# SparkFun_Ultrasonic_Sensor.net
KiCad netlist of a schematic drawn in EAGLE
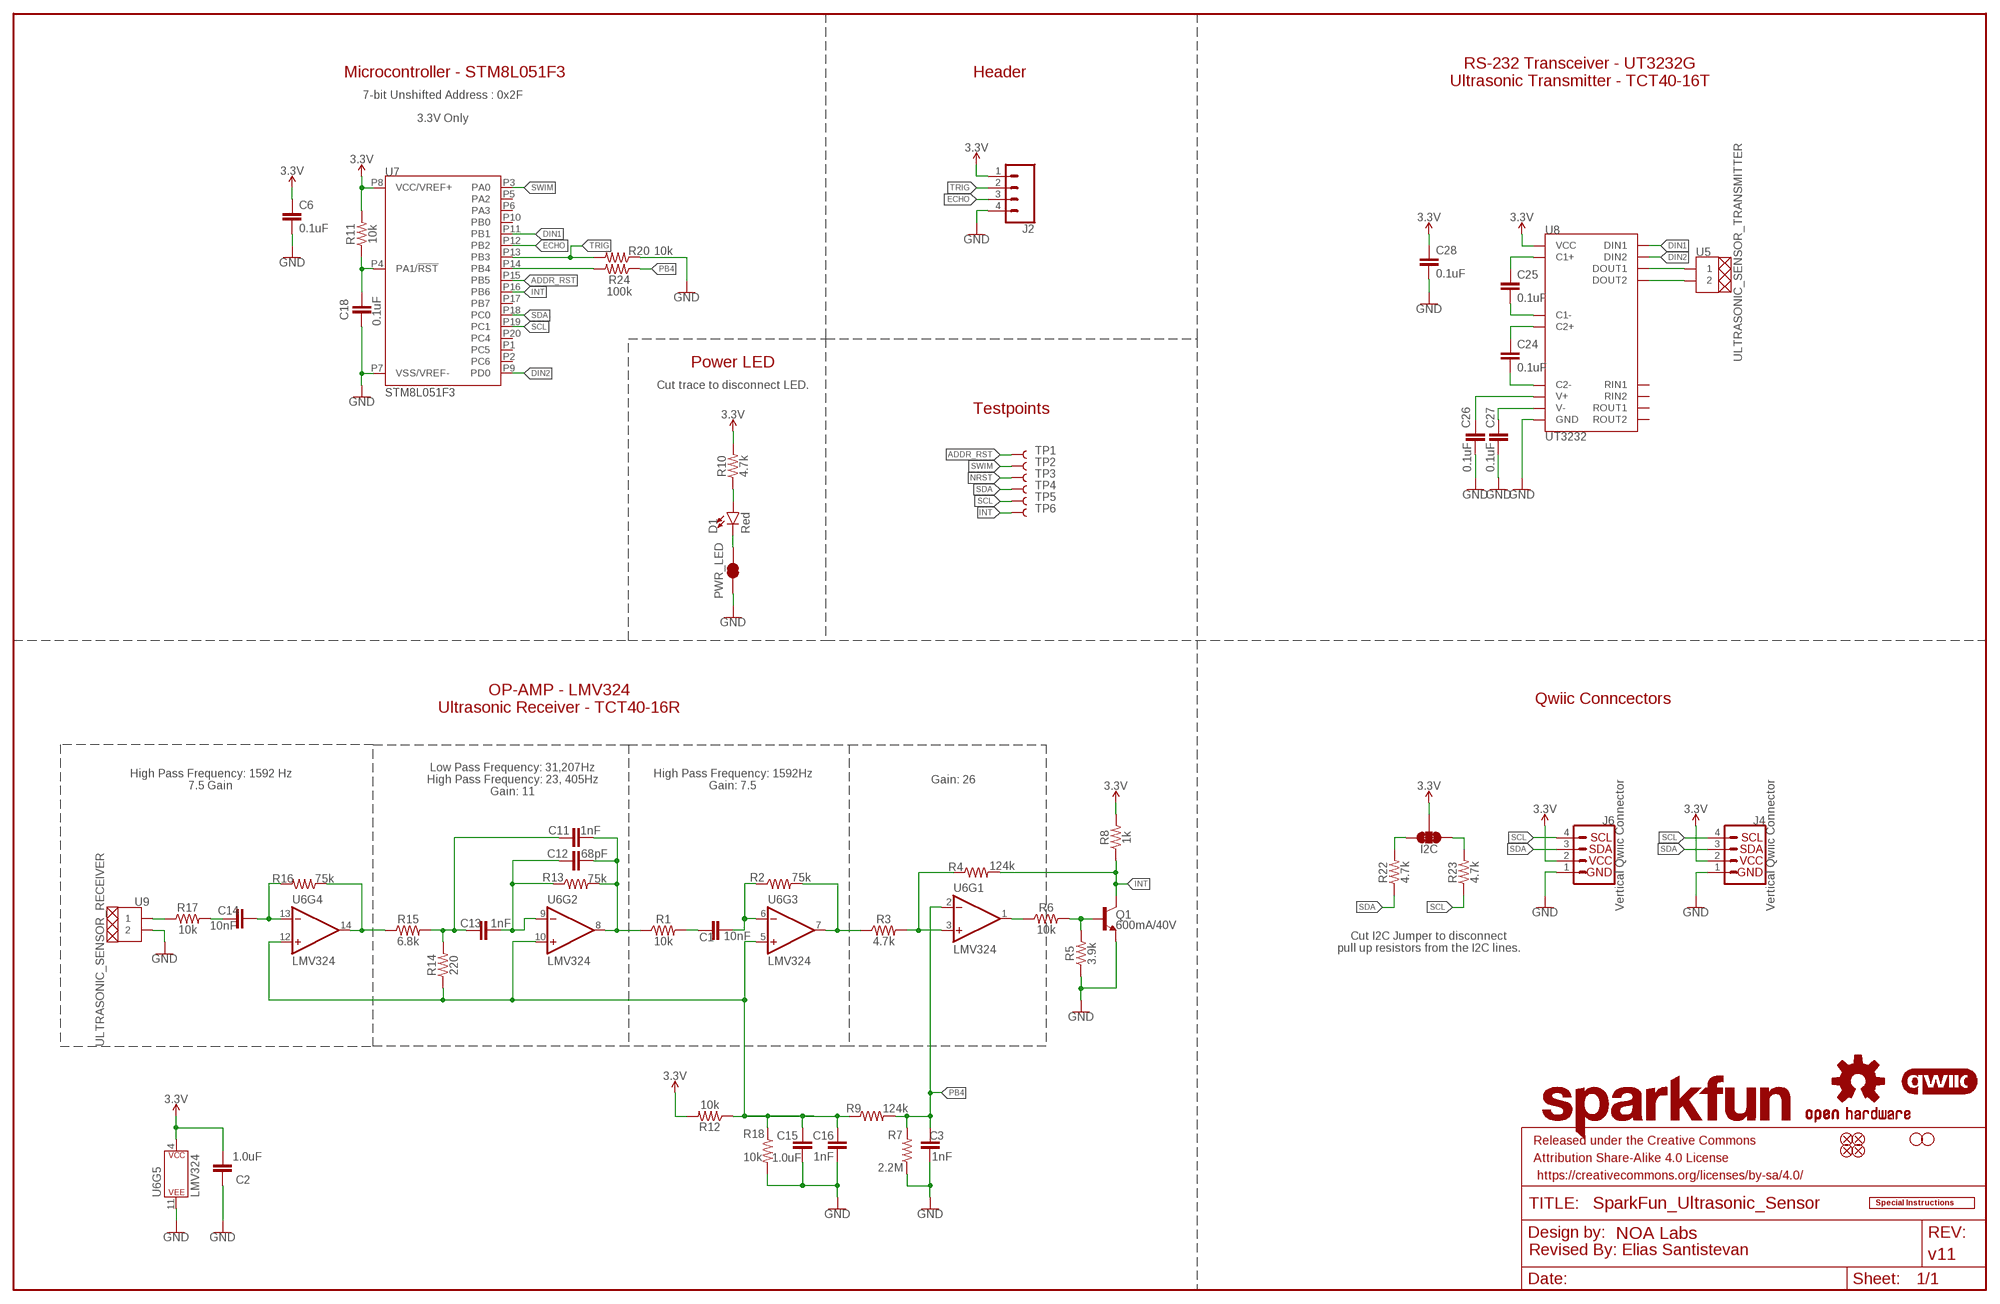
[diagram p0: schematic, sheet 1]

(export (version "E")
  (design (tool "Eeschema 10.0.6"))
  (components
    (comp (ref "C1")
      (value "10nF")
      (footprint "eagle-import:0603")
      (libsource (lib "eagle-import") (part "10NF-0603-50V-10%"))
    )
    (comp (ref "C2")
      (value "1.0uF")
      (footprint "eagle-import:0603")
      (libsource (lib "eagle-import") (part "1.0UF-0603-16V-10%"))
    )
    (comp (ref "C3")
      (value "1nF")
      (footprint "eagle-import:0603")
      (libsource (lib "eagle-import") (part "1.0NF/1000PF-0603-50V-10%"))
    )
    (comp (ref "C6")
      (value "0.1uF")
      (footprint "eagle-import:0603")
      (libsource (lib "eagle-import") (part "0.1UF-0603-25V-(+80/-20%)"))
    )
    (comp (ref "C11")
      (value "1nF")
      (footprint "eagle-import:0603")
      (libsource (lib "eagle-import") (part "1.0NF/1000PF-0603-50V-10%"))
    )
    (comp (ref "C12")
      (value "68pF")
      (footprint "eagle-import:0603")
      (libsource (lib "eagle-import") (part "68PF-0603-50V-5%"))
    )
    (comp (ref "C13")
      (value "1nF")
      (footprint "eagle-import:0603")
      (libsource (lib "eagle-import") (part "1.0NF/1000PF-0603-50V-10%"))
    )
    (comp (ref "C14")
      (value "10nF")
      (footprint "eagle-import:0603")
      (libsource (lib "eagle-import") (part "10NF-0603-50V-10%"))
    )
    (comp (ref "C15")
      (value "1.0uF")
      (footprint "eagle-import:0603")
      (libsource (lib "eagle-import") (part "1.0UF-0603-16V-10%"))
    )
    (comp (ref "C16")
      (value "1nF")
      (footprint "eagle-import:0603")
      (libsource (lib "eagle-import") (part "1.0NF/1000PF-0603-50V-10%"))
    )
    (comp (ref "C18")
      (value "0.1uF")
      (footprint "eagle-import:0603")
      (libsource (lib "eagle-import") (part "0.1UF-0603-25V-(+80/-20%)"))
    )
    (comp (ref "C24")
      (value "0.1uF")
      (footprint "eagle-import:0603")
      (libsource (lib "eagle-import") (part "0.1UF-0603-25V-(+80/-20%)"))
    )
    (comp (ref "C25")
      (value "0.1uF")
      (footprint "eagle-import:0603")
      (libsource (lib "eagle-import") (part "0.1UF-0603-25V-(+80/-20%)"))
    )
    (comp (ref "C26")
      (value "0.1uF")
      (footprint "eagle-import:0603")
      (libsource (lib "eagle-import") (part "0.1UF-0603-25V-(+80/-20%)"))
    )
    (comp (ref "C27")
      (value "0.1uF")
      (footprint "eagle-import:0603")
      (libsource (lib "eagle-import") (part "0.1UF-0603-25V-(+80/-20%)"))
    )
    (comp (ref "C28")
      (value "0.1uF")
      (footprint "eagle-import:0603")
      (libsource (lib "eagle-import") (part "0.1UF-0603-25V-(+80/-20%)"))
    )
    (comp (ref "D1")
      (value "Red")
      (footprint "eagle-import:LED-0603")
      (libsource (lib "eagle-import") (part "LED-RED_0603-KB"))
    )
    (comp (ref "FD1")
      (value "FIDUCIAL1X2")
      (footprint "eagle-import:FIDUCIAL-1X2")
      (libsource (lib "eagle-import") (part "FIDUCIAL1X2"))
    )
    (comp (ref "FD2")
      (value "FIDUCIAL1X2")
      (footprint "eagle-import:FIDUCIAL-1X2")
      (libsource (lib "eagle-import") (part "FIDUCIAL1X2"))
    )
    (comp (ref "FD3")
      (value "FIDUCIAL1X2")
      (footprint "eagle-import:FIDUCIAL-1X2")
      (libsource (lib "eagle-import") (part "FIDUCIAL1X2"))
    )
    (comp (ref "FD4")
      (value "FIDUCIAL1X2")
      (footprint "eagle-import:FIDUCIAL-1X2")
      (libsource (lib "eagle-import") (part "FIDUCIAL1X2"))
    )
    (comp (ref "FRAME1")
      (value "FRAME-LEDGER")
      (footprint "eagle-import:CREATIVE_COMMONS")
      (fields (field (name "DESIGNER") "NOA Labs") (field (name "REV") "v11"))
      (libsource (lib "eagle-import") (part "FRAME-LEDGER"))
    )
    (comp (ref "H1")
      (value "STAND-OFFTIGHT")
      (footprint "eagle-import:STAND-OFF-TIGHT")
      (libsource (lib "eagle-import") (part "STAND-OFFTIGHT"))
    )
    (comp (ref "H2")
      (value "STAND-OFFTIGHT")
      (footprint "eagle-import:STAND-OFF-TIGHT")
      (libsource (lib "eagle-import") (part "STAND-OFFTIGHT"))
    )
    (comp (ref "I2C")
      (value "JUMPER-SMT_3_2-NC_TRACE_SILK")
      (footprint "eagle-import:SMT-JUMPER_3_2-NC_TRACE_SILK")
      (libsource (lib "eagle-import") (part "JUMPER-SMT_3_2-NC_TRACE_SILK"))
    )
    (comp (ref "J2")
      (value "CONN_041X04_NO_SILK_NO_POP")
      (footprint "eagle-import:1X04_NO_SILK")
      (libsource (lib "eagle-import") (part "CONN_041X04_NO_SILK_NO_POP"))
    )
    (comp (ref "J4")
      (value "Vertical Qwiic Connector")
      (footprint "eagle-import:JST04_1MM_VERT")
      (libsource (lib "eagle-import") (part "QWIIC_CONNECTOR"))
    )
    (comp (ref "J6")
      (value "Vertical Qwiic Connector")
      (footprint "eagle-import:JST04_1MM_VERT")
      (libsource (lib "eagle-import") (part "QWIIC_CONNECTOR"))
    )
    (comp (ref "LOGO1")
      (value "SPECIAL_INSTRUCTIONS-ORDERING")
      (footprint "eagle-import:ORDERING_INSTRUCTIONS")
      (libsource (lib "eagle-import") (part "SPECIAL_INSTRUCTIONS-ORDERING"))
    )
    (comp (ref "LOGO2")
      (value "SFE_LOGO_NAME.1_INCH")
      (footprint "eagle-import:SFE_LOGO_NAME_.1")
      (libsource (lib "eagle-import") (part "SFE_LOGO_NAME.1_INCH"))
    )
    (comp (ref "LOGO3")
      (value "QWIIC_LOGO_3MM")
      (footprint "eagle-import:QWIIC_3MM")
      (libsource (lib "eagle-import") (part "QWIIC_LOGO_3MM"))
    )
    (comp (ref "LOGO4")
      (value "OSHW-LOGOS")
      (footprint "eagle-import:OSHW-LOGO-S")
      (libsource (lib "eagle-import") (part "OSHW-LOGOS"))
    )
    (comp (ref "PWR_LED")
      (value "JUMPER-SMT_2_NC_TRACE_SILK")
      (footprint "eagle-import:SMT-JUMPER_2_NC_TRACE_SILK")
      (libsource (lib "eagle-import") (part "JUMPER-SMT_2_NC_TRACE_SILK"))
    )
    (comp (ref "Q1")
      (value "600mA/40V")
      (footprint "eagle-import:SOT23-3")
      (libsource (lib "eagle-import") (part "TRANS_NPN-MMBT2222AL"))
    )
    (comp (ref "R1")
      (value "10k")
      (footprint "eagle-import:0603")
      (libsource (lib "eagle-import") (part "10KOHM-0603-1/10W-1%"))
    )
    (comp (ref "R2")
      (value "75k")
      (footprint "eagle-import:0603")
      (libsource (lib "eagle-import") (part "75KOHM-0603-1/10W-1%"))
    )
    (comp (ref "R3")
      (value "4.7k")
      (footprint "eagle-import:0603")
      (libsource (lib "eagle-import") (part "4.7KOHM-0603-1/10W-1%"))
    )
    (comp (ref "R4")
      (value "124k")
      (footprint "eagle-import:0603")
      (libsource (lib "eagle-import") (part "124KOHM"))
    )
    (comp (ref "R5")
      (value "3.9k")
      (footprint "eagle-import:0603")
      (libsource (lib "eagle-import") (part "3.9KOHM-0603-1/10W-1%"))
    )
    (comp (ref "R6")
      (value "10k")
      (footprint "eagle-import:0603")
      (libsource (lib "eagle-import") (part "10KOHM-0603-1/10W-1%"))
    )
    (comp (ref "R7")
      (value "2.2M")
      (footprint "eagle-import:0603")
      (libsource (lib "eagle-import") (part "2.2MOHMS-0603-1/10W-1%"))
    )
    (comp (ref "R8")
      (value "1k")
      (footprint "eagle-import:0603")
      (libsource (lib "eagle-import") (part "1KOHM-0603-1/10W-1%"))
    )
    (comp (ref "R9")
      (value "124k")
      (footprint "eagle-import:0603")
      (libsource (lib "eagle-import") (part "124KOHM"))
    )
    (comp (ref "R10")
      (value "4.7k")
      (footprint "eagle-import:0603")
      (libsource (lib "eagle-import") (part "4.7KOHM-0603-1/10W-1%"))
    )
    (comp (ref "R11")
      (value "10k")
      (footprint "eagle-import:0603")
      (libsource (lib "eagle-import") (part "10KOHM-0603-1/10W-1%"))
    )
    (comp (ref "R12")
      (value "10k")
      (footprint "eagle-import:0603")
      (libsource (lib "eagle-import") (part "10KOHM-0603-1/10W-1%"))
    )
    (comp (ref "R13")
      (value "75k")
      (footprint "eagle-import:0603")
      (libsource (lib "eagle-import") (part "75KOHM-0603-1/10W-1%"))
    )
    (comp (ref "R14")
      (value "220")
      (footprint "eagle-import:0603")
      (libsource (lib "eagle-import") (part "220OHM-0603-1/10W-1%"))
    )
    (comp (ref "R15")
      (value "6.8k")
      (footprint "eagle-import:0603")
      (libsource (lib "eagle-import") (part "6.8KOHM-0603-1/10W-1%"))
    )
    (comp (ref "R16")
      (value "75k")
      (footprint "eagle-import:0603")
      (libsource (lib "eagle-import") (part "75KOHM-0603-1/10W-1%"))
    )
    (comp (ref "R17")
      (value "10k")
      (footprint "eagle-import:0603")
      (libsource (lib "eagle-import") (part "10KOHM-0603-1/10W-1%"))
    )
    (comp (ref "R18")
      (value "10k")
      (footprint "eagle-import:0603")
      (libsource (lib "eagle-import") (part "10KOHM-0603-1/10W-1%"))
    )
    (comp (ref "R20")
      (value "10k")
      (footprint "eagle-import:0603")
      (libsource (lib "eagle-import") (part "10KOHM-0603-1/10W-1%"))
    )
    (comp (ref "R22")
      (value "4.7k")
      (footprint "eagle-import:0603")
      (libsource (lib "eagle-import") (part "4.7KOHM-0603-1/10W-1%"))
    )
    (comp (ref "R23")
      (value "4.7k")
      (footprint "eagle-import:0603")
      (libsource (lib "eagle-import") (part "4.7KOHM-0603-1/10W-1%"))
    )
    (comp (ref "R24")
      (value "100k")
      (footprint "eagle-import:0603")
      (libsource (lib "eagle-import") (part "100KOHM-0603-1/10W-1%"))
    )
    (comp (ref "TP1")
      (value "TEST-POINT3X5")
      (footprint "eagle-import:PAD.03X.05")
      (libsource (lib "eagle-import") (part "TEST-POINT3X5"))
    )
    (comp (ref "TP2")
      (value "TEST-POINT3X5")
      (footprint "eagle-import:PAD.03X.05")
      (libsource (lib "eagle-import") (part "TEST-POINT3X5"))
    )
    (comp (ref "TP3")
      (value "TEST-POINT3X5")
      (footprint "eagle-import:PAD.03X.05")
      (libsource (lib "eagle-import") (part "TEST-POINT3X5"))
    )
    (comp (ref "TP4")
      (value "TEST-POINT3X5")
      (footprint "eagle-import:PAD.03X.05")
      (libsource (lib "eagle-import") (part "TEST-POINT3X5"))
    )
    (comp (ref "TP5")
      (value "TEST-POINT3X5")
      (footprint "eagle-import:PAD.03X.05")
      (libsource (lib "eagle-import") (part "TEST-POINT3X5"))
    )
    (comp (ref "TP6")
      (value "TEST-POINT3X5")
      (footprint "eagle-import:PAD.03X.05")
      (libsource (lib "eagle-import") (part "TEST-POINT3X5"))
    )
    (comp (ref "U5")
      (value "ULTRASONIC_SENSOR_TRANSMITTER")
      (footprint "eagle-import:TFT40-16T")
      (libsource (lib "eagle-import") (part "ULTRASONIC_SENSOR_TRANSMITTER"))
    )
    (comp (ref "U6")
      (value "LMV324")
      (footprint "eagle-import:SO14")
      (libsource (lib "eagle-import") (part "LMV324"))
    )
    (comp (ref "U7")
      (value "STM8L051F3")
      (footprint "eagle-import:TSSOP20")
      (libsource (lib "eagle-import") (part "STM8L051F3"))
    )
    (comp (ref "U8")
      (value "UT3232")
      (footprint "eagle-import:TSSOP16")
      (libsource (lib "eagle-import") (part "UT3232"))
    )
    (comp (ref "U9")
      (value "ULTRASONIC_SENSOR_RECEIVER")
      (footprint "eagle-import:TCT40-16R")
      (libsource (lib "eagle-import") (part "ULTRASONIC_SENSOR_RECEIVER"))
    )
  )
  (nets
    (net (code "1") (name "3.3V") (class "Default")
      (node (ref "C2") (pin "2") (pinfunction "2_2") (pintype "passive"))
      (node (ref "C28") (pin "1") (pinfunction "1_1") (pintype "passive"))
      (node (ref "C6") (pin "1") (pinfunction "1_1") (pintype "passive"))
      (node (ref "I2C") (pin "2") (pinfunction "2_2") (pintype "passive"))
      (node (ref "J2") (pin "1") (pinfunction "1_1") (pintype "passive"))
      (node (ref "J4") (pin "2") (pinfunction "2_2") (pintype "power_in"))
      (node (ref "J6") (pin "2") (pinfunction "2_2") (pintype "power_in"))
      (node (ref "R10") (pin "2") (pinfunction "2_2") (pintype "passive"))
      (node (ref "R11") (pin "2") (pinfunction "2_2") (pintype "passive"))
      (node (ref "R12") (pin "2") (pinfunction "2_2") (pintype "passive"))
      (node (ref "R8") (pin "2") (pinfunction "2_2") (pintype "passive"))
      (node (ref "U6") (pin "4") (pinfunction "P$V+_4") (pintype "bidirectional"))
      (node (ref "U7") (pin "P8") (pinfunction "VCC/VREF+_P8") (pintype "bidirectional"))
      (node (ref "U8") (pin "P16") (pinfunction "VCC_P16") (pintype "bidirectional"))
    )
    (net (code "2") (name "ADDR_RST") (class "Default")
      (node (ref "TP1") (pin "1") (pinfunction "1_1") (pintype "bidirectional"))
      (node (ref "U7") (pin "P15") (pinfunction "PB5_P15") (pintype "bidirectional"))
    )
    (net (code "3") (name "DIN1") (class "Default")
      (node (ref "U7") (pin "P11") (pinfunction "PB1_P11") (pintype "bidirectional"))
      (node (ref "U8") (pin "P11") (pinfunction "DIN1_P11") (pintype "bidirectional"))
    )
    (net (code "4") (name "DIN2") (class "Default")
      (node (ref "U7") (pin "P9") (pinfunction "PD0_P9") (pintype "bidirectional"))
      (node (ref "U8") (pin "P10") (pinfunction "DIN2_P10") (pintype "bidirectional"))
    )
    (net (code "5") (name "ECHO") (class "Default")
      (node (ref "J2") (pin "3") (pinfunction "3_3") (pintype "passive"))
      (node (ref "U7") (pin "P12") (pinfunction "PB2_P12") (pintype "bidirectional"))
    )
    (net (code "6") (name "GND") (class "Default")
      (node (ref "C15") (pin "1") (pinfunction "1_1") (pintype "passive"))
      (node (ref "C16") (pin "1") (pinfunction "1_1") (pintype "passive"))
      (node (ref "C18") (pin "2") (pinfunction "2_2") (pintype "passive"))
      (node (ref "C2") (pin "1") (pinfunction "1_1") (pintype "passive"))
      (node (ref "C26") (pin "2") (pinfunction "2_2") (pintype "passive"))
      (node (ref "C27") (pin "2") (pinfunction "2_2") (pintype "passive"))
      (node (ref "C28") (pin "2") (pinfunction "2_2") (pintype "passive"))
      (node (ref "C3") (pin "2") (pinfunction "2_2") (pintype "passive"))
      (node (ref "C6") (pin "2") (pinfunction "2_2") (pintype "passive"))
      (node (ref "J2") (pin "4") (pinfunction "4_4") (pintype "passive"))
      (node (ref "J4") (pin "1") (pinfunction "1_1") (pintype "power_in"))
      (node (ref "J6") (pin "1") (pinfunction "1_1") (pintype "power_in"))
      (node (ref "PWR_LED") (pin "1") (pinfunction "1_1") (pintype "passive"))
      (node (ref "Q1") (pin "2") (pinfunction "E_2") (pintype "passive"))
      (node (ref "R18") (pin "2") (pinfunction "2_2") (pintype "passive"))
      (node (ref "R20") (pin "1") (pinfunction "1_1") (pintype "passive"))
      (node (ref "R5") (pin "1") (pinfunction "1_1") (pintype "passive"))
      (node (ref "R7") (pin "1") (pinfunction "1_1") (pintype "passive"))
      (node (ref "U6") (pin "11") (pinfunction "P$V-_11") (pintype "bidirectional"))
      (node (ref "U7") (pin "P7") (pinfunction "VSS/VREF-_P7") (pintype "bidirectional"))
      (node (ref "U8") (pin "P15") (pinfunction "GND_P15") (pintype "bidirectional"))
      (node (ref "U9") (pin "P2") (pinfunction "2_P2") (pintype "bidirectional"))
    )
    (net (code "7") (name "INT") (class "Default")
      (node (ref "Q1") (pin "3") (pinfunction "C_3") (pintype "passive"))
      (node (ref "R4") (pin "2") (pinfunction "2_2") (pintype "passive"))
      (node (ref "R8") (pin "1") (pinfunction "1_1") (pintype "passive"))
      (node (ref "TP6") (pin "1") (pinfunction "1_1") (pintype "bidirectional"))
      (node (ref "U7") (pin "P16") (pinfunction "PB6_P16") (pintype "bidirectional"))
    )
    (net (code "8") (name "NRST") (class "Default")
      (node (ref "C18") (pin "1") (pinfunction "1_1") (pintype "passive"))
      (node (ref "R11") (pin "1") (pinfunction "1_1") (pintype "passive"))
      (node (ref "TP3") (pin "1") (pinfunction "1_1") (pintype "bidirectional"))
      (node (ref "U7") (pin "P4") (pinfunction "PA1/~{RST}_P4") (pintype "bidirectional"))
    )
    (net (code "9") (name "Net-(C1-Pad2)") (class "Default")
      (node (ref "C1") (pin "2") (pinfunction "2_2") (pintype "passive"))
      (node (ref "R1") (pin "2") (pinfunction "2_2") (pintype "passive"))
    )
    (net (code "10") (name "Net-(C11-Pad1)") (class "Default")
      (node (ref "C11") (pin "1") (pinfunction "1_1") (pintype "passive"))
      (node (ref "C13") (pin "2") (pinfunction "2_2") (pintype "passive"))
      (node (ref "R14") (pin "2") (pinfunction "2_2") (pintype "passive"))
      (node (ref "R15") (pin "2") (pinfunction "2_2") (pintype "passive"))
    )
    (net (code "11") (name "Net-(C14-Pad2)") (class "Default")
      (node (ref "C14") (pin "2") (pinfunction "2_2") (pintype "passive"))
      (node (ref "R17") (pin "2") (pinfunction "2_2") (pintype "passive"))
    )
    (net (code "12") (name "Net-(D1-PadA)") (class "Default")
      (node (ref "D1") (pin "A") (pinfunction "A_A") (pintype "passive"))
      (node (ref "R10") (pin "1") (pinfunction "1_1") (pintype "passive"))
    )
    (net (code "13") (name "Net-(D1-PadC)") (class "Default")
      (node (ref "D1") (pin "C") (pinfunction "C_C") (pintype "passive"))
      (node (ref "PWR_LED") (pin "2") (pinfunction "2_2") (pintype "passive"))
    )
    (net (code "14") (name "Net-(I2C-Pad1)") (class "Default")
      (node (ref "I2C") (pin "1") (pinfunction "1_1") (pintype "passive"))
      (node (ref "R23") (pin "2") (pinfunction "2_2") (pintype "passive"))
    )
    (net (code "15") (name "Net-(I2C-Pad3)") (class "Default")
      (node (ref "I2C") (pin "3") (pinfunction "3_3") (pintype "passive"))
      (node (ref "R22") (pin "2") (pinfunction "2_2") (pintype "passive"))
    )
    (net (code "16") (name "Net-(Q1-B)") (class "Default")
      (node (ref "Q1") (pin "1") (pinfunction "B_1") (pintype "passive"))
      (node (ref "R5") (pin "2") (pinfunction "2_2") (pintype "passive"))
      (node (ref "R6") (pin "2") (pinfunction "2_2") (pintype "passive"))
    )
    (net (code "17") (name "Net-(U5-1)") (class "Default")
      (node (ref "U5") (pin "P1") (pinfunction "1_P1") (pintype "bidirectional"))
      (node (ref "U8") (pin "P14") (pinfunction "DOUT1_P14") (pintype "bidirectional"))
    )
    (net (code "18") (name "Net-(U5-2)") (class "Default")
      (node (ref "U5") (pin "P2") (pinfunction "2_P2") (pintype "bidirectional"))
      (node (ref "U8") (pin "P7") (pinfunction "DOUT2_P7") (pintype "bidirectional"))
    )
    (net (code "19") (name "Net-(U6A-+IN)") (class "Default")
      (node (ref "R3") (pin "2") (pinfunction "2_2") (pintype "passive"))
      (node (ref "R4") (pin "1") (pinfunction "1_1") (pintype "passive"))
      (node (ref "U6") (pin "3") (pinfunction "+IN_3") (pintype "input"))
    )
    (net (code "20") (name "Net-(U6A-OUT)") (class "Default")
      (node (ref "R6") (pin "1") (pinfunction "1_1") (pintype "passive"))
      (node (ref "U6") (pin "1") (pinfunction "OUT_1") (pintype "output"))
    )
    (net (code "21") (name "Net-(U6B-+IN)") (class "Default")
      (node (ref "C15") (pin "2") (pinfunction "2_2") (pintype "passive"))
      (node (ref "C16") (pin "2") (pinfunction "2_2") (pintype "passive"))
      (node (ref "R12") (pin "1") (pinfunction "1_1") (pintype "passive"))
      (node (ref "R14") (pin "1") (pinfunction "1_1") (pintype "passive"))
      (node (ref "R18") (pin "1") (pinfunction "1_1") (pintype "passive"))
      (node (ref "R9") (pin "1") (pinfunction "1_1") (pintype "passive"))
      (node (ref "U6") (pin "10") (pinfunction "+IN_10") (pintype "input"))
      (node (ref "U6") (pin "12") (pinfunction "+IN_12") (pintype "input"))
      (node (ref "U6") (pin "5") (pinfunction "+IN_5") (pintype "input"))
    )
    (net (code "22") (name "Net-(U6B--IN)") (class "Default")
      (node (ref "C12") (pin "1") (pinfunction "1_1") (pintype "passive"))
      (node (ref "C13") (pin "1") (pinfunction "1_1") (pintype "passive"))
      (node (ref "R13") (pin "1") (pinfunction "1_1") (pintype "passive"))
      (node (ref "U6") (pin "9") (pinfunction "-IN_9") (pintype "input"))
    )
    (net (code "23") (name "Net-(U6B-OUT)") (class "Default")
      (node (ref "C11") (pin "2") (pinfunction "2_2") (pintype "passive"))
      (node (ref "C12") (pin "2") (pinfunction "2_2") (pintype "passive"))
      (node (ref "R1") (pin "1") (pinfunction "1_1") (pintype "passive"))
      (node (ref "R13") (pin "2") (pinfunction "2_2") (pintype "passive"))
      (node (ref "U6") (pin "8") (pinfunction "OUT_8") (pintype "output"))
    )
    (net (code "24") (name "Net-(U6C--IN)") (class "Default")
      (node (ref "C1") (pin "1") (pinfunction "1_1") (pintype "passive"))
      (node (ref "R2") (pin "1") (pinfunction "1_1") (pintype "passive"))
      (node (ref "U6") (pin "6") (pinfunction "-IN_6") (pintype "input"))
    )
    (net (code "25") (name "Net-(U6C-OUT)") (class "Default")
      (node (ref "R2") (pin "2") (pinfunction "2_2") (pintype "passive"))
      (node (ref "R3") (pin "1") (pinfunction "1_1") (pintype "passive"))
      (node (ref "U6") (pin "7") (pinfunction "OUT_7") (pintype "output"))
    )
    (net (code "26") (name "Net-(U6D--IN)") (class "Default")
      (node (ref "C14") (pin "1") (pinfunction "1_1") (pintype "passive"))
      (node (ref "R16") (pin "2") (pinfunction "2_2") (pintype "passive"))
      (node (ref "U6") (pin "13") (pinfunction "-IN_13") (pintype "input"))
    )
    (net (code "27") (name "Net-(U6D-OUT)") (class "Default")
      (node (ref "R15") (pin "1") (pinfunction "1_1") (pintype "passive"))
      (node (ref "R16") (pin "1") (pinfunction "1_1") (pintype "passive"))
      (node (ref "U6") (pin "14") (pinfunction "OUT_14") (pintype "output"))
    )
    (net (code "28") (name "Net-(U7-PB4)") (class "Default")
      (node (ref "R24") (pin "2") (pinfunction "2_2") (pintype "passive"))
      (node (ref "U7") (pin "P14") (pinfunction "PB4_P14") (pintype "bidirectional"))
    )
    (net (code "29") (name "Net-(U8-C1+)") (class "Default")
      (node (ref "C25") (pin "1") (pinfunction "1_1") (pintype "passive"))
      (node (ref "U8") (pin "P1") (pinfunction "C1+_P1") (pintype "bidirectional"))
    )
    (net (code "30") (name "Net-(U8-C1-)") (class "Default")
      (node (ref "C25") (pin "2") (pinfunction "2_2") (pintype "passive"))
      (node (ref "U8") (pin "P3") (pinfunction "C1-_P3") (pintype "bidirectional"))
    )
    (net (code "31") (name "Net-(U8-C2+)") (class "Default")
      (node (ref "C24") (pin "1") (pinfunction "1_1") (pintype "passive"))
      (node (ref "U8") (pin "P4") (pinfunction "C2+_P4") (pintype "bidirectional"))
    )
    (net (code "32") (name "Net-(U8-C2-)") (class "Default")
      (node (ref "C24") (pin "2") (pinfunction "2_2") (pintype "passive"))
      (node (ref "U8") (pin "P5") (pinfunction "C2-_P5") (pintype "bidirectional"))
    )
    (net (code "33") (name "Net-(U8-V+)") (class "Default")
      (node (ref "C26") (pin "1") (pinfunction "1_1") (pintype "passive"))
      (node (ref "U8") (pin "P2") (pinfunction "V+_P2") (pintype "bidirectional"))
    )
    (net (code "34") (name "Net-(U8-V-)") (class "Default")
      (node (ref "C27") (pin "1") (pinfunction "1_1") (pintype "passive"))
      (node (ref "U8") (pin "P6") (pinfunction "V-_P6") (pintype "bidirectional"))
    )
    (net (code "35") (name "Net-(U9-1)") (class "Default")
      (node (ref "R17") (pin "1") (pinfunction "1_1") (pintype "passive"))
      (node (ref "U9") (pin "P1") (pinfunction "1_P1") (pintype "bidirectional"))
    )
    (net (code "36") (name "PB4") (class "Default")
      (node (ref "C3") (pin "1") (pinfunction "1_1") (pintype "passive"))
      (node (ref "R24") (pin "1") (pinfunction "1_1") (pintype "passive"))
      (node (ref "R7") (pin "2") (pinfunction "2_2") (pintype "passive"))
      (node (ref "R9") (pin "2") (pinfunction "2_2") (pintype "passive"))
      (node (ref "U6") (pin "2") (pinfunction "-IN_2") (pintype "input"))
    )
    (net (code "37") (name "SCL") (class "Default")
      (node (ref "J4") (pin "4") (pinfunction "4_4") (pintype "passive"))
      (node (ref "J6") (pin "4") (pinfunction "4_4") (pintype "passive"))
      (node (ref "R23") (pin "1") (pinfunction "1_1") (pintype "passive"))
      (node (ref "TP5") (pin "1") (pinfunction "1_1") (pintype "bidirectional"))
      (node (ref "U7") (pin "P19") (pinfunction "PC1_P19") (pintype "bidirectional"))
    )
    (net (code "38") (name "SDA") (class "Default")
      (node (ref "J4") (pin "3") (pinfunction "3_3") (pintype "passive"))
      (node (ref "J6") (pin "3") (pinfunction "3_3") (pintype "passive"))
      (node (ref "R22") (pin "1") (pinfunction "1_1") (pintype "passive"))
      (node (ref "TP4") (pin "1") (pinfunction "1_1") (pintype "bidirectional"))
      (node (ref "U7") (pin "P18") (pinfunction "PC0_P18") (pintype "bidirectional"))
    )
    (net (code "39") (name "SWIM") (class "Default")
      (node (ref "TP2") (pin "1") (pinfunction "1_1") (pintype "bidirectional"))
      (node (ref "U7") (pin "P3") (pinfunction "PA0_P3") (pintype "bidirectional"))
    )
    (net (code "40") (name "TRIG") (class "Default")
      (node (ref "J2") (pin "2") (pinfunction "2_2") (pintype "passive"))
      (node (ref "R20") (pin "2") (pinfunction "2_2") (pintype "passive"))
      (node (ref "U7") (pin "P13") (pinfunction "PB3_P13") (pintype "bidirectional"))
    )
    (net (code "41") (name "unconnected-(U7-PA2-PadP5)") (class "Default")
      (node (ref "U7") (pin "P5") (pinfunction "PA2_P5") (pintype "bidirectional"))
    )
    (net (code "42") (name "unconnected-(U7-PA3-PadP6)") (class "Default")
      (node (ref "U7") (pin "P6") (pinfunction "PA3_P6") (pintype "bidirectional"))
    )
    (net (code "43") (name "unconnected-(U7-PB0-PadP10)") (class "Default")
      (node (ref "U7") (pin "P10") (pinfunction "PB0_P10") (pintype "bidirectional"))
    )
    (net (code "44") (name "unconnected-(U7-PB7-PadP17)") (class "Default")
      (node (ref "U7") (pin "P17") (pinfunction "PB7_P17") (pintype "bidirectional"))
    )
    (net (code "45") (name "unconnected-(U7-PC4-PadP20)") (class "Default")
      (node (ref "U7") (pin "P20") (pinfunction "PC4_P20") (pintype "bidirectional"))
    )
    (net (code "46") (name "unconnected-(U7-PC5-PadP1)") (class "Default")
      (node (ref "U7") (pin "P1") (pinfunction "PC5_P1") (pintype "bidirectional"))
    )
    (net (code "47") (name "unconnected-(U7-PC6-PadP2)") (class "Default")
      (node (ref "U7") (pin "P2") (pinfunction "PC6_P2") (pintype "bidirectional"))
    )
    (net (code "48") (name "unconnected-(U8-RIN1-PadP13)") (class "Default")
      (node (ref "U8") (pin "P13") (pinfunction "RIN1_P13") (pintype "bidirectional"))
    )
    (net (code "49") (name "unconnected-(U8-RIN2-PadP8)") (class "Default")
      (node (ref "U8") (pin "P8") (pinfunction "RIN2_P8") (pintype "bidirectional"))
    )
    (net (code "50") (name "unconnected-(U8-ROUT1-PadP12)") (class "Default")
      (node (ref "U8") (pin "P12") (pinfunction "ROUT1_P12") (pintype "bidirectional"))
    )
    (net (code "51") (name "unconnected-(U8-ROUT2-PadP9)") (class "Default")
      (node (ref "U8") (pin "P9") (pinfunction "ROUT2_P9") (pintype "bidirectional"))
    )
  )
)
